# Unregulated_DC_Power_Supply.net
KiCad netlist of a schematic drawn in EAGLE
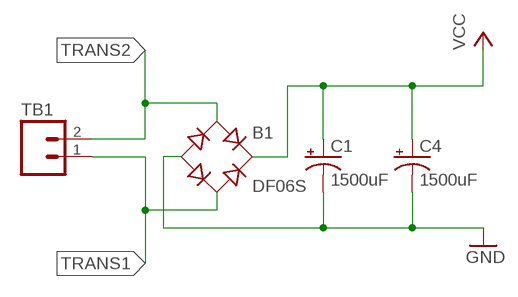
[diagram p0: schematic, sheet 1]

(export (version "E")
  (design (tool "Eeschema 10.0.6"))
  (components
    (comp (ref "B1")
      (value "DF06S")
      (footprint "eagle-import:DFS")
      (libsource (lib "eagle-import") (part "DFS06"))
    )
    (comp (ref "C1")
      (value "1500uF")
      (footprint "eagle-import:CAP_J16")
      (libsource (lib "eagle-import") (part "CAP_POL_J16"))
    )
    (comp (ref "C4")
      (value "1500uF")
      (footprint "eagle-import:CAP_J16")
      (libsource (lib "eagle-import") (part "CAP_POL_J16"))
    )
    (comp (ref "TB1")
      (value "TERMINAL_BLOCK_2")
      (footprint "eagle-import:TERMINL_BLOCK_2_POS")
      (libsource (lib "eagle-import") (part "TERMINAL_BLOCK_2"))
    )
  )
  (nets
    (net (code "1") (name "GND") (class "Default")
      (node (ref "B1") (pin "-") (pinfunction "-_-") (pintype "passive"))
      (node (ref "C1") (pin "1") (pinfunction "-_1") (pintype "passive"))
      (node (ref "C4") (pin "1") (pinfunction "-_1") (pintype "passive"))
    )
    (net (code "2") (name "TRANS1") (class "Default")
      (node (ref "B1") (pin "AC2") (pinfunction "AC2_AC2") (pintype "passive"))
      (node (ref "TB1") (pin "1") (pinfunction "1_1") (pintype "passive"))
    )
    (net (code "3") (name "TRANS2") (class "Default")
      (node (ref "B1") (pin "AC1") (pinfunction "AC1_AC1") (pintype "passive"))
      (node (ref "TB1") (pin "2") (pinfunction "2_2") (pintype "passive"))
    )
    (net (code "4") (name "VCC") (class "Default")
      (node (ref "B1") (pin "+") (pinfunction "+_+") (pintype "passive"))
      (node (ref "C1") (pin "2") (pinfunction "+_2") (pintype "passive"))
      (node (ref "C4") (pin "2") (pinfunction "+_2") (pintype "passive"))
    )
  )
)
